# vi_measurement.net
KiCad netlist of a schematic drawn in Altium Designer
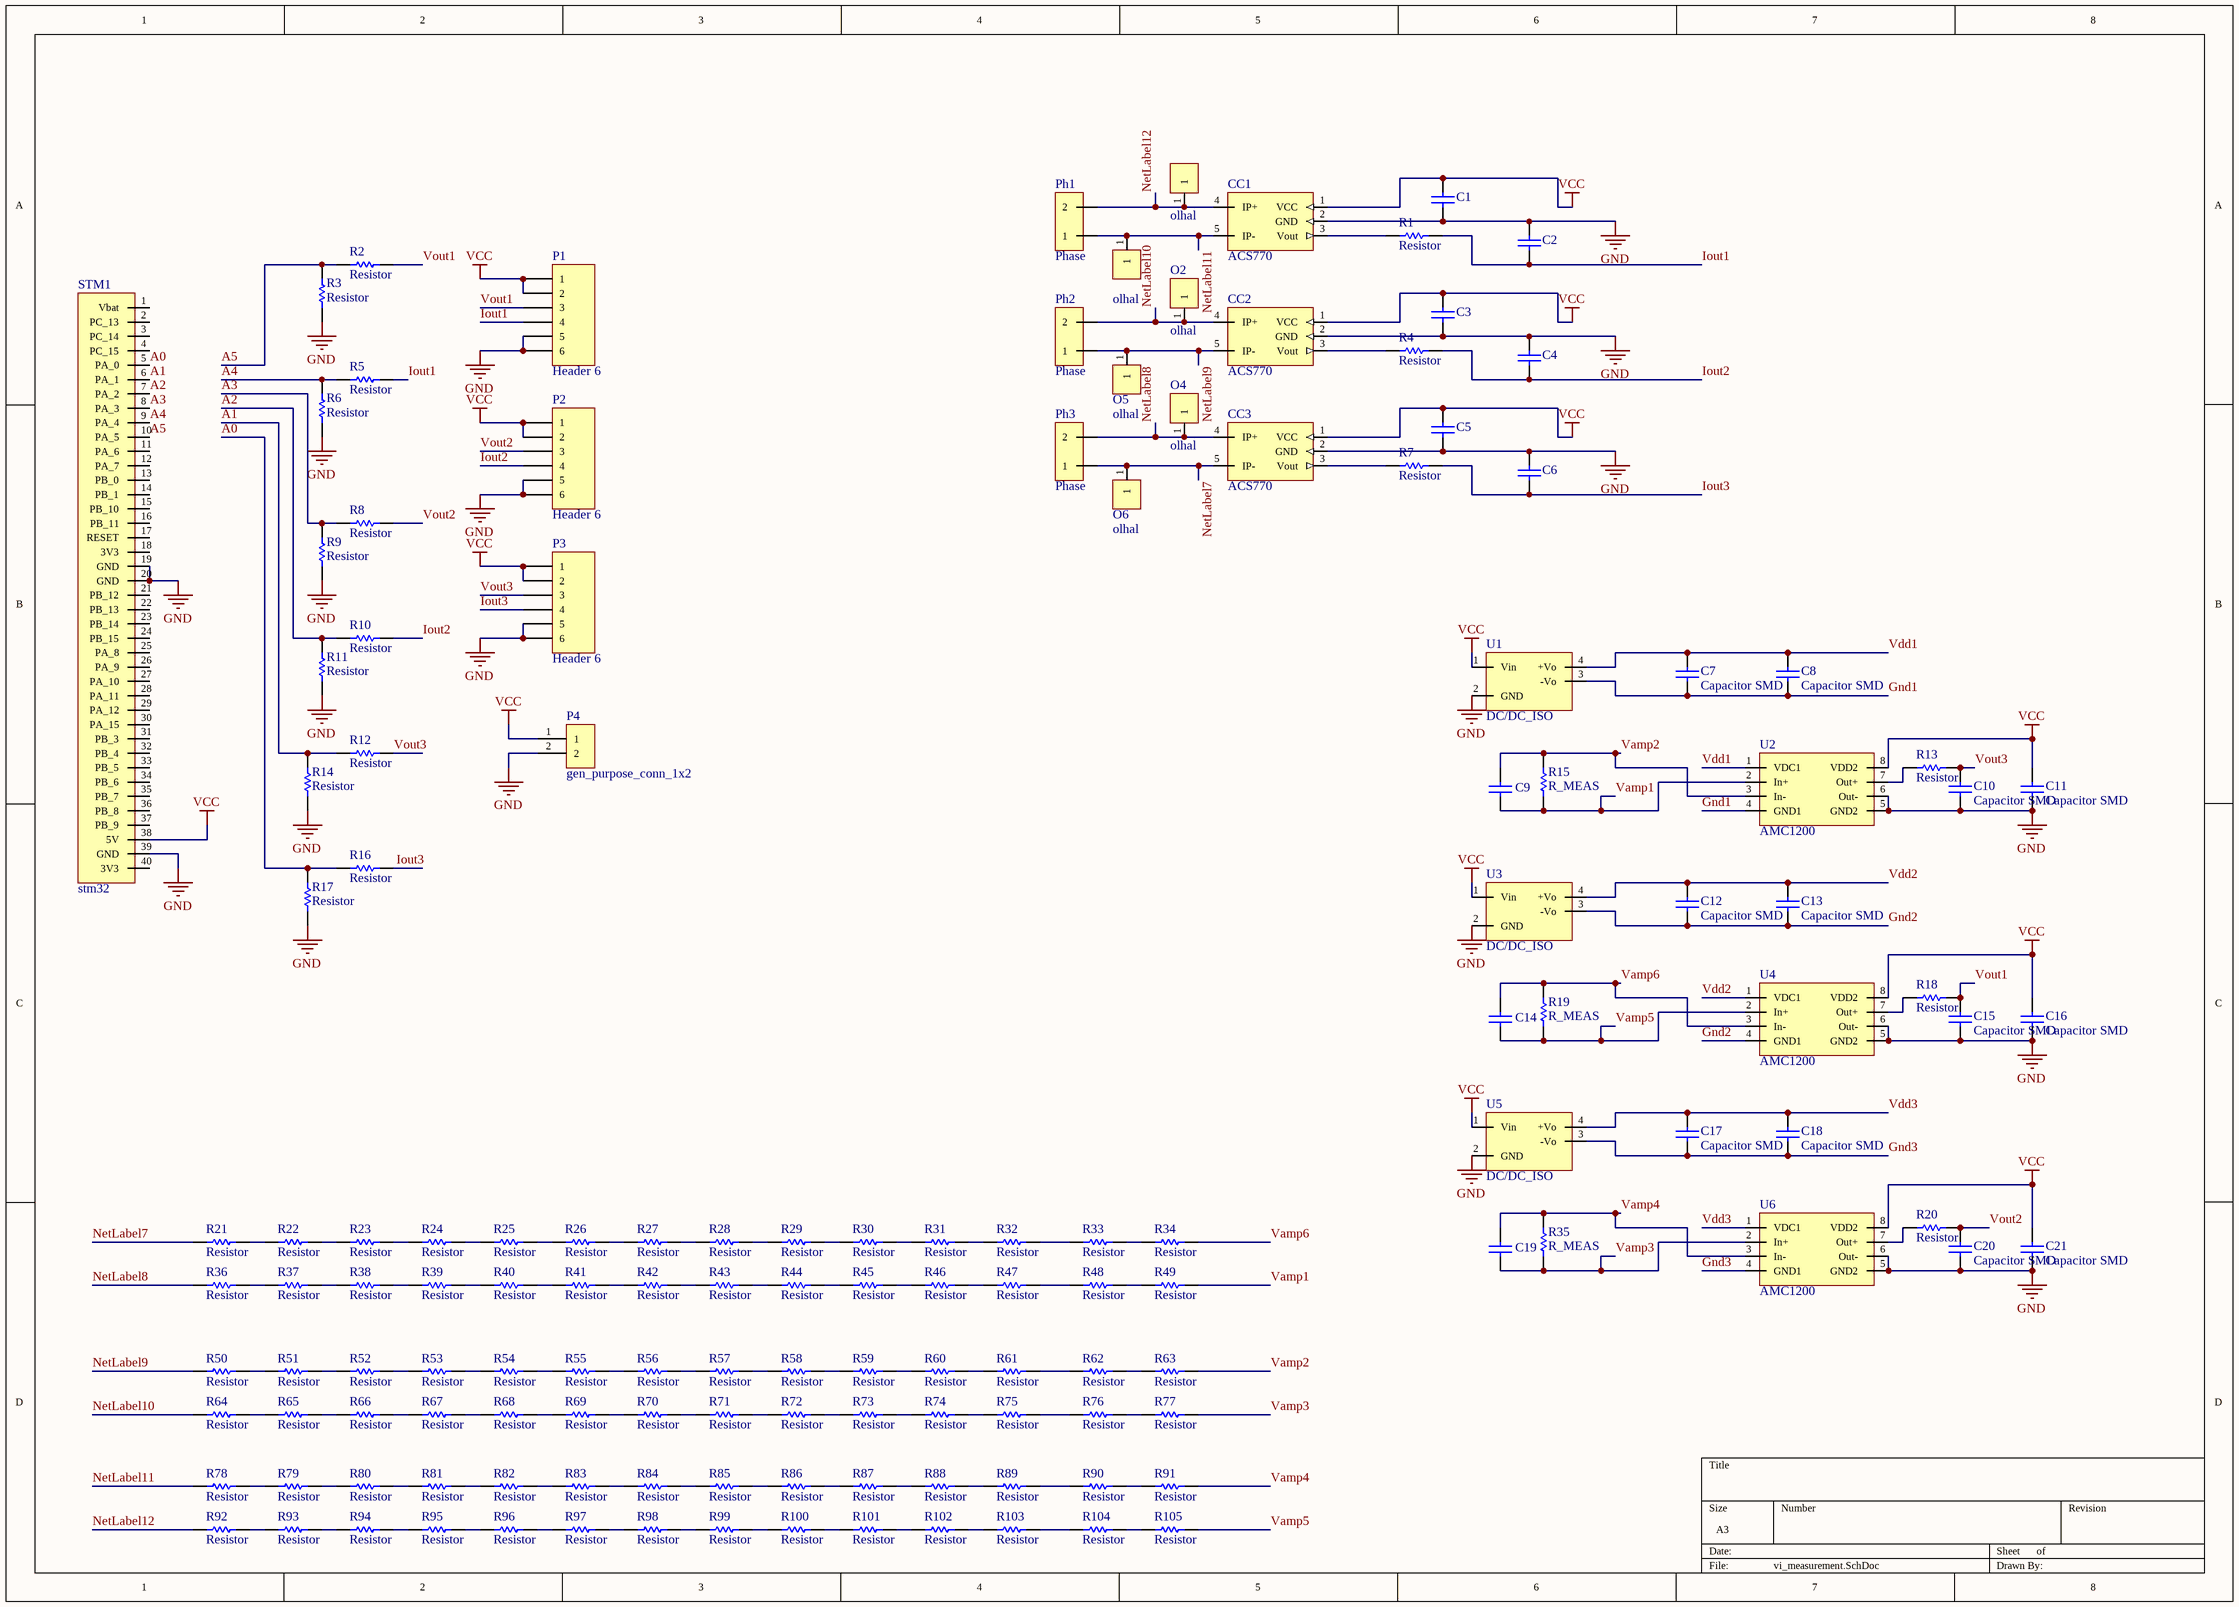
[diagram p0: vi_measurement.SchDoc]

(export (version "E")
  (design (tool "Eeschema 10.0.6"))
  (components
    (comp (ref "C1")
      (value "~")
      (footprint "CAPC_0805")
      (description "10uF")
      (libsource (lib "inversor_50a") (part "Capacitor SMD"))
    )
    (comp (ref "C2")
      (value "~")
      (footprint "CAPC_0805")
      (description "1uF")
      (libsource (lib "inversor_50a") (part "Capacitor SMD"))
    )
    (comp (ref "C3")
      (value "~")
      (footprint "CAPC_0805")
      (description "10uF")
      (libsource (lib "inversor_50a") (part "Capacitor SMD"))
    )
    (comp (ref "C4")
      (value "~")
      (footprint "CAPC_0805")
      (description "1uF")
      (libsource (lib "inversor_50a") (part "Capacitor SMD"))
    )
    (comp (ref "C5")
      (value "~")
      (footprint "CAPC_0805")
      (description "10uF")
      (libsource (lib "inversor_50a") (part "Capacitor SMD"))
    )
    (comp (ref "C6")
      (value "~")
      (footprint "CAPC_0805")
      (description "1uF")
      (libsource (lib "inversor_50a") (part "Capacitor SMD"))
    )
    (comp (ref "C7")
      (value "Capacitor SMD")
      (footprint "CAPC_0805")
      (description "10uF")
      (libsource (lib "vi_measurement") (part "Capacitor SMD"))
    )
    (comp (ref "C8")
      (value "Capacitor SMD")
      (footprint "CAPC_0805")
      (description "10uF")
      (libsource (lib "vi_measurement") (part "Capacitor SMD"))
    )
    (comp (ref "C9")
      (value "Capacitor SMD")
      (footprint "CAPC_0805")
      (description "1uF")
      (libsource (lib "vi_measurement") (part "Capacitor SMD"))
    )
    (comp (ref "C10")
      (value "Capacitor SMD")
      (footprint "CAPC_0805")
      (description "1uF")
      (libsource (lib "vi_measurement") (part "Capacitor SMD"))
    )
    (comp (ref "C11")
      (value "Capacitor SMD")
      (footprint "CAPC_0805")
      (description "10uF")
      (libsource (lib "vi_measurement") (part "Capacitor SMD"))
    )
    (comp (ref "C12")
      (value "Capacitor SMD")
      (footprint "CAPC_0805")
      (description "10uF")
      (libsource (lib "vi_measurement") (part "Capacitor SMD"))
    )
    (comp (ref "C13")
      (value "Capacitor SMD")
      (footprint "CAPC_0805")
      (description "10uF")
      (libsource (lib "vi_measurement") (part "Capacitor SMD"))
    )
    (comp (ref "C14")
      (value "Capacitor SMD")
      (footprint "CAPC_0805")
      (description "1uF")
      (libsource (lib "vi_measurement") (part "Capacitor SMD"))
    )
    (comp (ref "C15")
      (value "Capacitor SMD")
      (footprint "CAPC_0805")
      (description "1uF")
      (libsource (lib "vi_measurement") (part "Capacitor SMD"))
    )
    (comp (ref "C16")
      (value "Capacitor SMD")
      (footprint "CAPC_0805")
      (description "10uF")
      (libsource (lib "vi_measurement") (part "Capacitor SMD"))
    )
    (comp (ref "C17")
      (value "Capacitor SMD")
      (footprint "CAPC_0805")
      (description "10uF")
      (libsource (lib "vi_measurement") (part "Capacitor SMD"))
    )
    (comp (ref "C18")
      (value "Capacitor SMD")
      (footprint "CAPC_0805")
      (description "10uF")
      (libsource (lib "vi_measurement") (part "Capacitor SMD"))
    )
    (comp (ref "C19")
      (value "Capacitor SMD")
      (footprint "CAPC_0805")
      (description "1uF")
      (libsource (lib "vi_measurement") (part "Capacitor SMD"))
    )
    (comp (ref "C20")
      (value "Capacitor SMD")
      (footprint "CAPC_0805")
      (description "1uF")
      (libsource (lib "vi_measurement") (part "Capacitor SMD"))
    )
    (comp (ref "C21")
      (value "Capacitor SMD")
      (footprint "CAPC_0805")
      (description "10uF")
      (libsource (lib "vi_measurement") (part "Capacitor SMD"))
    )
    (comp (ref "CC1") (value "ACS770") (footprint "ACS770") (libsource (lib "malvega_pcb") (part "ACS770")))
    (comp (ref "CC2") (value "ACS770") (footprint "ACS770") (libsource (lib "malvega_pcb") (part "ACS770")))
    (comp (ref "CC3") (value "ACS770") (footprint "ACS770") (libsource (lib "malvega_pcb") (part "ACS770")))
    (comp (ref "O1") (value "olhal") (footprint "Olhal") (libsource (lib "") (part "olhal_1")))
    (comp (ref "O2") (value "olhal") (footprint "Olhal") (libsource (lib "") (part "olhal_1")))
    (comp (ref "O3") (value "olhal") (footprint "Olhal") (libsource (lib "vi_measurement") (part "olhal")))
    (comp (ref "O4") (value "olhal") (footprint "Olhal") (libsource (lib "") (part "olhal_1")))
    (comp (ref "O5") (value "olhal") (footprint "Olhal") (libsource (lib "vi_measurement") (part "olhal")))
    (comp (ref "O6") (value "olhal") (footprint "Olhal") (libsource (lib "vi_measurement") (part "olhal")))
    (comp (ref "P1")
      (value "Header 6")
      (footprint "HDR1X6")
      (description "Header, 6-Pin")
      (fields (field (name "PUBLISHER") "Altium Limited"))
      (libsource (lib "malvega_pcb") (part "Header 6"))
    )
    (comp (ref "P2")
      (value "Header 6")
      (footprint "HDR1X6")
      (description "Header, 6-Pin")
      (fields (field (name "PUBLISHER") "Altium Limited"))
      (libsource (lib "malvega_pcb") (part "Header 6"))
    )
    (comp (ref "P3")
      (value "Header 6")
      (footprint "HDR1X6")
      (description "Header, 6-Pin")
      (fields (field (name "PUBLISHER") "Altium Limited"))
      (libsource (lib "malvega_pcb") (part "Header 6"))
    )
    (comp (ref "P4")
      (value "gen_purpose_conn_1x2")
      (footprint "connector1x2_parafuso")
      (libsource (lib "malvega_pcb") (part "gen_purpose_conn_1x2"))
    )
    (comp (ref "Ph1") (value "Phase") (footprint "Phoenix") (libsource (lib "malvega_pcb") (part "Phoenix")))
    (comp (ref "Ph2") (value "Phase") (footprint "Phoenix") (libsource (lib "malvega_pcb") (part "Phoenix")))
    (comp (ref "Ph3") (value "Phase") (footprint "Phoenix") (libsource (lib "malvega_pcb") (part "Phoenix")))
    (comp (ref "R1")
      (value "Resistor")
      (footprint "RESC_0805")
      (description "330R")
      (libsource (lib "inversor_50a") (part "Resistor"))
    )
    (comp (ref "R2")
      (value "Resistor")
      (footprint "RESC_0805")
      (description "5K")
      (libsource (lib "inversor_50a") (part "Resistor"))
    )
    (comp (ref "R3")
      (value "Resistor")
      (footprint "RESC_0805")
      (description "7K5")
      (libsource (lib "inversor_50a") (part "Resistor"))
    )
    (comp (ref "R4")
      (value "Resistor")
      (footprint "RESC_0805")
      (description "330R")
      (libsource (lib "inversor_50a") (part "Resistor"))
    )
    (comp (ref "R5")
      (value "Resistor")
      (footprint "RESC_0805")
      (description "5K")
      (libsource (lib "inversor_50a") (part "Resistor"))
    )
    (comp (ref "R6")
      (value "Resistor")
      (footprint "RESC_0805")
      (description "7K5")
      (libsource (lib "inversor_50a") (part "Resistor"))
    )
    (comp (ref "R7")
      (value "Resistor")
      (footprint "RESC_0805")
      (description "330R")
      (libsource (lib "inversor_50a") (part "Resistor"))
    )
    (comp (ref "R8")
      (value "Resistor")
      (footprint "RESC_0805")
      (description "5K")
      (libsource (lib "inversor_50a") (part "Resistor"))
    )
    (comp (ref "R9")
      (value "Resistor")
      (footprint "RESC_0805")
      (description "7K5")
      (libsource (lib "inversor_50a") (part "Resistor"))
    )
    (comp (ref "R10")
      (value "Resistor")
      (footprint "RESC_0805")
      (description "5K")
      (libsource (lib "inversor_50a") (part "Resistor"))
    )
    (comp (ref "R11")
      (value "Resistor")
      (footprint "RESC_0805")
      (description "7K5")
      (libsource (lib "inversor_50a") (part "Resistor"))
    )
    (comp (ref "R12")
      (value "Resistor")
      (footprint "RESC_0805")
      (description "5K")
      (libsource (lib "inversor_50a") (part "Resistor"))
    )
    (comp (ref "R13")
      (value "Resistor")
      (footprint "RESC_0805")
      (description "330R")
      (libsource (lib "inversor_50a") (part "Resistor"))
    )
    (comp (ref "R14")
      (value "Resistor")
      (footprint "RESC_0805")
      (description "7K5")
      (libsource (lib "inversor_50a") (part "Resistor"))
    )
    (comp (ref "R15")
      (value "R_MEAS")
      (footprint "RESC_0805")
      (description "200R")
      (libsource (lib "inversor_50a") (part "Resistor"))
    )
    (comp (ref "R16")
      (value "Resistor")
      (footprint "RESC_0805")
      (description "5K")
      (libsource (lib "inversor_50a") (part "Resistor"))
    )
    (comp (ref "R17")
      (value "Resistor")
      (footprint "RESC_0805")
      (description "7K5")
      (libsource (lib "inversor_50a") (part "Resistor"))
    )
    (comp (ref "R18")
      (value "Resistor")
      (footprint "RESC_0805")
      (description "330R")
      (libsource (lib "inversor_50a") (part "Resistor"))
    )
    (comp (ref "R19")
      (value "R_MEAS")
      (footprint "RESC_0805")
      (description "200R")
      (libsource (lib "inversor_50a") (part "Resistor"))
    )
    (comp (ref "R20")
      (value "Resistor")
      (footprint "RESC_0805")
      (description "330R")
      (libsource (lib "inversor_50a") (part "Resistor"))
    )
    (comp (ref "R21")
      (value "Resistor")
      (footprint "RESC_0805")
      (description "7K5")
      (libsource (lib "inversor_50a") (part "Resistor"))
    )
    (comp (ref "R22")
      (value "Resistor")
      (footprint "RESC_0805")
      (libsource (lib "inversor_50a") (part "Resistor"))
    )
    (comp (ref "R23")
      (value "Resistor")
      (footprint "RESC_0805")
      (libsource (lib "inversor_50a") (part "Resistor"))
    )
    (comp (ref "R24")
      (value "Resistor")
      (footprint "RESC_0805")
      (libsource (lib "inversor_50a") (part "Resistor"))
    )
    (comp (ref "R25")
      (value "Resistor")
      (footprint "RESC_0805")
      (libsource (lib "inversor_50a") (part "Resistor"))
    )
    (comp (ref "R26")
      (value "Resistor")
      (footprint "RESC_0805")
      (libsource (lib "inversor_50a") (part "Resistor"))
    )
    (comp (ref "R27")
      (value "Resistor")
      (footprint "RESC_0805")
      (libsource (lib "inversor_50a") (part "Resistor"))
    )
    (comp (ref "R28")
      (value "Resistor")
      (footprint "RESC_0805")
      (libsource (lib "inversor_50a") (part "Resistor"))
    )
    (comp (ref "R29")
      (value "Resistor")
      (footprint "RESC_0805")
      (libsource (lib "inversor_50a") (part "Resistor"))
    )
    (comp (ref "R30")
      (value "Resistor")
      (footprint "RESC_0805")
      (libsource (lib "inversor_50a") (part "Resistor"))
    )
    (comp (ref "R31")
      (value "Resistor")
      (footprint "RESC_0805")
      (libsource (lib "inversor_50a") (part "Resistor"))
    )
    (comp (ref "R32")
      (value "Resistor")
      (footprint "RESC_0805")
      (libsource (lib "inversor_50a") (part "Resistor"))
    )
    (comp (ref "R33")
      (value "Resistor")
      (footprint "RESC_0805")
      (libsource (lib "inversor_50a") (part "Resistor"))
    )
    (comp (ref "R34")
      (value "Resistor")
      (footprint "RESC_0805")
      (libsource (lib "inversor_50a") (part "Resistor"))
    )
    (comp (ref "R35")
      (value "R_MEAS")
      (footprint "RESC_0805")
      (description "200R")
      (libsource (lib "inversor_50a") (part "Resistor"))
    )
    (comp (ref "R36")
      (value "Resistor")
      (footprint "RESC_0805")
      (description "7K5")
      (libsource (lib "inversor_50a") (part "Resistor"))
    )
    (comp (ref "R37")
      (value "Resistor")
      (footprint "RESC_0805")
      (description "7K5")
      (libsource (lib "inversor_50a") (part "Resistor"))
    )
    (comp (ref "R38")
      (value "Resistor")
      (footprint "RESC_0805")
      (description "7K5")
      (libsource (lib "inversor_50a") (part "Resistor"))
    )
    (comp (ref "R39")
      (value "Resistor")
      (footprint "RESC_0805")
      (description "7K5")
      (libsource (lib "inversor_50a") (part "Resistor"))
    )
    (comp (ref "R40")
      (value "Resistor")
      (footprint "RESC_0805")
      (description "7K5")
      (libsource (lib "inversor_50a") (part "Resistor"))
    )
    (comp (ref "R41")
      (value "Resistor")
      (footprint "RESC_0805")
      (description "7K5")
      (libsource (lib "inversor_50a") (part "Resistor"))
    )
    (comp (ref "R42")
      (value "Resistor")
      (footprint "RESC_0805")
      (description "7K5")
      (libsource (lib "inversor_50a") (part "Resistor"))
    )
    (comp (ref "R43")
      (value "Resistor")
      (footprint "RESC_0805")
      (description "7K5")
      (libsource (lib "inversor_50a") (part "Resistor"))
    )
    (comp (ref "R44")
      (value "Resistor")
      (footprint "RESC_0805")
      (description "7K5")
      (libsource (lib "inversor_50a") (part "Resistor"))
    )
    (comp (ref "R45")
      (value "Resistor")
      (footprint "RESC_0805")
      (description "7K5")
      (libsource (lib "inversor_50a") (part "Resistor"))
    )
    (comp (ref "R46")
      (value "Resistor")
      (footprint "RESC_0805")
      (description "7K5")
      (libsource (lib "inversor_50a") (part "Resistor"))
    )
    (comp (ref "R47")
      (value "Resistor")
      (footprint "RESC_0805")
      (description "7K5")
      (libsource (lib "inversor_50a") (part "Resistor"))
    )
    (comp (ref "R48")
      (value "Resistor")
      (footprint "RESC_0805")
      (description "7K5")
      (libsource (lib "inversor_50a") (part "Resistor"))
    )
    (comp (ref "R49")
      (value "Resistor")
      (footprint "RESC_0805")
      (description "7K5")
      (libsource (lib "inversor_50a") (part "Resistor"))
    )
    (comp (ref "R50")
      (value "Resistor")
      (footprint "RESC_0805")
      (description "7K5")
      (libsource (lib "inversor_50a") (part "Resistor"))
    )
    (comp (ref "R51")
      (value "Resistor")
      (footprint "RESC_0805")
      (description "7K5")
      (libsource (lib "inversor_50a") (part "Resistor"))
    )
    (comp (ref "R52")
      (value "Resistor")
      (footprint "RESC_0805")
      (description "7K5")
      (libsource (lib "inversor_50a") (part "Resistor"))
    )
    (comp (ref "R53")
      (value "Resistor")
      (footprint "RESC_0805")
      (description "7K5")
      (libsource (lib "inversor_50a") (part "Resistor"))
    )
    (comp (ref "R54")
      (value "Resistor")
      (footprint "RESC_0805")
      (description "7K5")
      (libsource (lib "inversor_50a") (part "Resistor"))
    )
    (comp (ref "R55")
      (value "Resistor")
      (footprint "RESC_0805")
      (description "7K5")
      (libsource (lib "inversor_50a") (part "Resistor"))
    )
    (comp (ref "R56")
      (value "Resistor")
      (footprint "RESC_0805")
      (description "7K5")
      (libsource (lib "inversor_50a") (part "Resistor"))
    )
    (comp (ref "R57")
      (value "Resistor")
      (footprint "RESC_0805")
      (description "7K5")
      (libsource (lib "inversor_50a") (part "Resistor"))
    )
    (comp (ref "R58")
      (value "Resistor")
      (footprint "RESC_0805")
      (description "7K5")
      (libsource (lib "inversor_50a") (part "Resistor"))
    )
    (comp (ref "R59")
      (value "Resistor")
      (footprint "RESC_0805")
      (description "7K5")
      (libsource (lib "inversor_50a") (part "Resistor"))
    )
    (comp (ref "R60")
      (value "Resistor")
      (footprint "RESC_0805")
      (description "7K5")
      (libsource (lib "inversor_50a") (part "Resistor"))
    )
    (comp (ref "R61")
      (value "Resistor")
      (footprint "RESC_0805")
      (description "7K5")
      (libsource (lib "inversor_50a") (part "Resistor"))
    )
    (comp (ref "R62")
      (value "Resistor")
      (footprint "RESC_0805")
      (description "7K5")
      (libsource (lib "inversor_50a") (part "Resistor"))
    )
    (comp (ref "R63")
      (value "Resistor")
      (footprint "RESC_0805")
      (description "7K5")
      (libsource (lib "inversor_50a") (part "Resistor"))
    )
    (comp (ref "R64")
      (value "Resistor")
      (footprint "RESC_0805")
      (description "7K5")
      (libsource (lib "inversor_50a") (part "Resistor"))
    )
    (comp (ref "R65")
      (value "Resistor")
      (footprint "RESC_0805")
      (description "7K5")
      (libsource (lib "inversor_50a") (part "Resistor"))
    )
    (comp (ref "R66")
      (value "Resistor")
      (footprint "RESC_0805")
      (description "7K5")
      (libsource (lib "inversor_50a") (part "Resistor"))
    )
    (comp (ref "R67")
      (value "Resistor")
      (footprint "RESC_0805")
      (description "7K5")
      (libsource (lib "inversor_50a") (part "Resistor"))
    )
    (comp (ref "R68")
      (value "Resistor")
      (footprint "RESC_0805")
      (description "7K5")
      (libsource (lib "inversor_50a") (part "Resistor"))
    )
    (comp (ref "R69")
      (value "Resistor")
      (footprint "RESC_0805")
      (description "7K5")
      (libsource (lib "inversor_50a") (part "Resistor"))
    )
    (comp (ref "R70")
      (value "Resistor")
      (footprint "RESC_0805")
      (description "7K5")
      (libsource (lib "inversor_50a") (part "Resistor"))
    )
    (comp (ref "R71")
      (value "Resistor")
      (footprint "RESC_0805")
      (description "7K5")
      (libsource (lib "inversor_50a") (part "Resistor"))
    )
    (comp (ref "R72")
      (value "Resistor")
      (footprint "RESC_0805")
      (description "7K5")
      (libsource (lib "inversor_50a") (part "Resistor"))
    )
    (comp (ref "R73")
      (value "Resistor")
      (footprint "RESC_0805")
      (description "7K5")
      (libsource (lib "inversor_50a") (part "Resistor"))
    )
    (comp (ref "R74")
      (value "Resistor")
      (footprint "RESC_0805")
      (description "7K5")
      (libsource (lib "inversor_50a") (part "Resistor"))
    )
    (comp (ref "R75")
      (value "Resistor")
      (footprint "RESC_0805")
      (description "7K5")
      (libsource (lib "inversor_50a") (part "Resistor"))
    )
    (comp (ref "R76")
      (value "Resistor")
      (footprint "RESC_0805")
      (description "7K5")
      (libsource (lib "inversor_50a") (part "Resistor"))
    )
    (comp (ref "R77")
      (value "Resistor")
      (footprint "RESC_0805")
      (description "7K5")
      (libsource (lib "inversor_50a") (part "Resistor"))
    )
    (comp (ref "R78")
      (value "Resistor")
      (footprint "RESC_0805")
      (description "7K5")
      (libsource (lib "inversor_50a") (part "Resistor"))
    )
    (comp (ref "R79")
      (value "Resistor")
      (footprint "RESC_0805")
      (description "7K5")
      (libsource (lib "inversor_50a") (part "Resistor"))
    )
    (comp (ref "R80")
      (value "Resistor")
      (footprint "RESC_0805")
      (description "7K5")
      (libsource (lib "inversor_50a") (part "Resistor"))
    )
    (comp (ref "R81")
      (value "Resistor")
      (footprint "RESC_0805")
      (description "7K5")
      (libsource (lib "inversor_50a") (part "Resistor"))
    )
    (comp (ref "R82")
      (value "Resistor")
      (footprint "RESC_0805")
      (description "7K5")
      (libsource (lib "inversor_50a") (part "Resistor"))
    )
    (comp (ref "R83")
      (value "Resistor")
      (footprint "RESC_0805")
      (description "7K5")
      (libsource (lib "inversor_50a") (part "Resistor"))
    )
    (comp (ref "R84")
      (value "Resistor")
      (footprint "RESC_0805")
      (description "7K5")
      (libsource (lib "inversor_50a") (part "Resistor"))
    )
    (comp (ref "R85")
      (value "Resistor")
      (footprint "RESC_0805")
      (description "7K5")
      (libsource (lib "inversor_50a") (part "Resistor"))
    )
    (comp (ref "R86")
      (value "Resistor")
      (footprint "RESC_0805")
      (description "7K5")
      (libsource (lib "inversor_50a") (part "Resistor"))
    )
    (comp (ref "R87")
      (value "Resistor")
      (footprint "RESC_0805")
      (description "7K5")
      (libsource (lib "inversor_50a") (part "Resistor"))
    )
    (comp (ref "R88")
      (value "Resistor")
      (footprint "RESC_0805")
      (description "7K5")
      (libsource (lib "inversor_50a") (part "Resistor"))
    )
    (comp (ref "R89")
      (value "Resistor")
      (footprint "RESC_0805")
      (description "7K5")
      (libsource (lib "inversor_50a") (part "Resistor"))
    )
    (comp (ref "R90")
      (value "Resistor")
      (footprint "RESC_0805")
      (description "7K5")
      (libsource (lib "inversor_50a") (part "Resistor"))
    )
    (comp (ref "R91")
      (value "Resistor")
      (footprint "RESC_0805")
      (description "7K5")
      (libsource (lib "inversor_50a") (part "Resistor"))
    )
    (comp (ref "R92")
      (value "Resistor")
      (footprint "RESC_0805")
      (description "7K5")
      (libsource (lib "inversor_50a") (part "Resistor"))
    )
    (comp (ref "R93")
      (value "Resistor")
      (footprint "RESC_0805")
      (description "7K5")
      (libsource (lib "inversor_50a") (part "Resistor"))
    )
    (comp (ref "R94")
      (value "Resistor")
      (footprint "RESC_0805")
      (description "7K5")
      (libsource (lib "inversor_50a") (part "Resistor"))
    )
    (comp (ref "R95")
      (value "Resistor")
      (footprint "RESC_0805")
      (description "7K5")
      (libsource (lib "inversor_50a") (part "Resistor"))
    )
    (comp (ref "R96")
      (value "Resistor")
      (footprint "RESC_0805")
      (description "7K5")
      (libsource (lib "inversor_50a") (part "Resistor"))
    )
    (comp (ref "R97")
      (value "Resistor")
      (footprint "RESC_0805")
      (description "7K5")
      (libsource (lib "inversor_50a") (part "Resistor"))
    )
    (comp (ref "R98")
      (value "Resistor")
      (footprint "RESC_0805")
      (description "7K5")
      (libsource (lib "inversor_50a") (part "Resistor"))
    )
    (comp (ref "R99")
      (value "Resistor")
      (footprint "RESC_0805")
      (description "7K5")
      (libsource (lib "inversor_50a") (part "Resistor"))
    )
    (comp (ref "R100")
      (value "Resistor")
      (footprint "RESC_0805")
      (description "7K5")
      (libsource (lib "inversor_50a") (part "Resistor"))
    )
    (comp (ref "R101")
      (value "Resistor")
      (footprint "RESC_0805")
      (description "7K5")
      (libsource (lib "inversor_50a") (part "Resistor"))
    )
    (comp (ref "R102")
      (value "Resistor")
      (footprint "RESC_0805")
      (description "7K5")
      (libsource (lib "inversor_50a") (part "Resistor"))
    )
    (comp (ref "R103")
      (value "Resistor")
      (footprint "RESC_0805")
      (description "7K5")
      (libsource (lib "inversor_50a") (part "Resistor"))
    )
    (comp (ref "R104")
      (value "Resistor")
      (footprint "RESC_0805")
      (description "7K5")
      (libsource (lib "inversor_50a") (part "Resistor"))
    )
    (comp (ref "R105")
      (value "Resistor")
      (footprint "RESC_0805")
      (description "7K5")
      (libsource (lib "inversor_50a") (part "Resistor"))
    )
    (comp (ref "STM1") (value "stm32") (footprint "STM32") (libsource (lib "vi_measurement") (part "stm32")))
    (comp (ref "U1")
      (value "DC/DC_ISO")
      (footprint "DC/DC_ISO")
      (libsource (lib "vi_measurement") (part "DC/DC_ISO"))
    )
    (comp (ref "U2")
      (value "AMC1200")
      (footprint "SOIC8")
      (libsource (lib "vi_measurement") (part "AMC1200"))
    )
    (comp (ref "U3")
      (value "DC/DC_ISO")
      (footprint "DC/DC_ISO")
      (libsource (lib "vi_measurement") (part "DC/DC_ISO"))
    )
    (comp (ref "U4")
      (value "AMC1200")
      (footprint "SOIC8")
      (libsource (lib "vi_measurement") (part "AMC1200"))
    )
    (comp (ref "U5")
      (value "DC/DC_ISO")
      (footprint "DC/DC_ISO")
      (libsource (lib "vi_measurement") (part "DC/DC_ISO"))
    )
    (comp (ref "U6")
      (value "AMC1200")
      (footprint "SOIC8")
      (libsource (lib "vi_measurement") (part "AMC1200"))
    )
  )
  (nets
    (net (code "1") (name "/A0") (class "Default")
      (node (ref "R16") (pin "1") (pinfunction "1_1") (pintype "passive"))
      (node (ref "R17") (pin "2") (pinfunction "2_2") (pintype "passive"))
      (node (ref "STM1") (pin "5") (pinfunction "PA_0_5") (pintype "passive"))
    )
    (net (code "2") (name "/A1") (class "Default")
      (node (ref "R12") (pin "1") (pinfunction "1_1") (pintype "passive"))
      (node (ref "R14") (pin "2") (pinfunction "2_2") (pintype "passive"))
      (node (ref "STM1") (pin "6") (pinfunction "PA_1_6") (pintype "passive"))
    )
    (net (code "3") (name "/A2") (class "Default")
      (node (ref "R10") (pin "1") (pinfunction "1_1") (pintype "passive"))
      (node (ref "R11") (pin "2") (pinfunction "2_2") (pintype "passive"))
      (node (ref "STM1") (pin "7") (pinfunction "PA_2_7") (pintype "passive"))
    )
    (net (code "4") (name "/A3") (class "Default")
      (node (ref "R8") (pin "1") (pinfunction "1_1") (pintype "passive"))
      (node (ref "R9") (pin "2") (pinfunction "2_2") (pintype "passive"))
      (node (ref "STM1") (pin "8") (pinfunction "PA_3_8") (pintype "passive"))
    )
    (net (code "5") (name "/A4") (class "Default")
      (node (ref "R5") (pin "1") (pinfunction "1_1") (pintype "passive"))
      (node (ref "R6") (pin "2") (pinfunction "2_2") (pintype "passive"))
      (node (ref "STM1") (pin "9") (pinfunction "PA_4_9") (pintype "passive"))
    )
    (net (code "6") (name "/A5") (class "Default")
      (node (ref "R2") (pin "1") (pinfunction "1_1") (pintype "passive"))
      (node (ref "R3") (pin "2") (pinfunction "2_2") (pintype "passive"))
      (node (ref "STM1") (pin "10") (pinfunction "PA_5_10") (pintype "passive"))
    )
    (net (code "7") (name "/Gnd1") (class "Default")
      (node (ref "C7") (pin "1") (pinfunction "1_1") (pintype "passive"))
      (node (ref "C8") (pin "1") (pinfunction "1_1") (pintype "passive"))
      (node (ref "U1") (pin "3") (pinfunction "-Vo_3") (pintype "passive"))
      (node (ref "U2") (pin "4") (pinfunction "GND1_4") (pintype "passive"))
    )
    (net (code "8") (name "/Gnd2") (class "Default")
      (node (ref "C12") (pin "1") (pinfunction "1_1") (pintype "passive"))
      (node (ref "C13") (pin "1") (pinfunction "1_1") (pintype "passive"))
      (node (ref "U3") (pin "3") (pinfunction "-Vo_3") (pintype "passive"))
      (node (ref "U4") (pin "4") (pinfunction "GND1_4") (pintype "passive"))
    )
    (net (code "9") (name "/Gnd3") (class "Default")
      (node (ref "C17") (pin "1") (pinfunction "1_1") (pintype "passive"))
      (node (ref "C18") (pin "1") (pinfunction "1_1") (pintype "passive"))
      (node (ref "U5") (pin "3") (pinfunction "-Vo_3") (pintype "passive"))
      (node (ref "U6") (pin "4") (pinfunction "GND1_4") (pintype "passive"))
    )
    (net (code "10") (name "/Iout1") (class "Default")
      (node (ref "C2") (pin "1") (pinfunction "1_1") (pintype "passive"))
      (node (ref "P1") (pin "4") (pinfunction "4_4") (pintype "passive"))
      (node (ref "R1") (pin "2") (pinfunction "2_2") (pintype "passive"))
      (node (ref "R5") (pin "2") (pinfunction "2_2") (pintype "passive"))
    )
    (net (code "11") (name "/Iout2") (class "Default")
      (node (ref "C4") (pin "1") (pinfunction "1_1") (pintype "passive"))
      (node (ref "P2") (pin "4") (pinfunction "4_4") (pintype "passive"))
      (node (ref "R10") (pin "2") (pinfunction "2_2") (pintype "passive"))
      (node (ref "R4") (pin "2") (pinfunction "2_2") (pintype "passive"))
    )
    (net (code "12") (name "/Iout3") (class "Default")
      (node (ref "C6") (pin "1") (pinfunction "1_1") (pintype "passive"))
      (node (ref "P3") (pin "4") (pinfunction "4_4") (pintype "passive"))
      (node (ref "R16") (pin "2") (pinfunction "2_2") (pintype "passive"))
      (node (ref "R7") (pin "2") (pinfunction "2_2") (pintype "passive"))
    )
    (net (code "13") (name "/NetLabel7") (class "Default")
      (node (ref "CC3") (pin "5") (pinfunction "IP-_5") (pintype "power_in"))
      (node (ref "O6") (pin "1") (pinfunction "1_1") (pintype "passive"))
      (node (ref "Ph3") (pin "1") (pinfunction "1_1") (pintype "passive"))
      (node (ref "R21") (pin "1") (pinfunction "1_1") (pintype "passive"))
    )
    (net (code "14") (name "/NetLabel8") (class "Default")
      (node (ref "CC3") (pin "4") (pinfunction "IP+_4") (pintype "power_in"))
      (node (ref "O4") (pin "1") (pinfunction "1_1") (pintype "passive"))
      (node (ref "Ph3") (pin "2") (pinfunction "2_2") (pintype "passive"))
      (node (ref "R36") (pin "1") (pinfunction "1_1") (pintype "passive"))
    )
    (net (code "15") (name "/NetLabel9") (class "Default")
      (node (ref "CC2") (pin "5") (pinfunction "IP-_5") (pintype "power_in"))
      (node (ref "O5") (pin "1") (pinfunction "1_1") (pintype "passive"))
      (node (ref "Ph2") (pin "1") (pinfunction "1_1") (pintype "passive"))
      (node (ref "R50") (pin "1") (pinfunction "1_1") (pintype "passive"))
    )
    (net (code "16") (name "/NetLabel10") (class "Default")
      (node (ref "CC2") (pin "4") (pinfunction "IP+_4") (pintype "power_in"))
      (node (ref "O2") (pin "1") (pinfunction "1_1") (pintype "passive"))
      (node (ref "Ph2") (pin "2") (pinfunction "2_2") (pintype "passive"))
      (node (ref "R64") (pin "1") (pinfunction "1_1") (pintype "passive"))
    )
    (net (code "17") (name "/NetLabel11") (class "Default")
      (node (ref "CC1") (pin "5") (pinfunction "IP-_5") (pintype "power_in"))
      (node (ref "O3") (pin "1") (pinfunction "1_1") (pintype "passive"))
      (node (ref "Ph1") (pin "1") (pinfunction "1_1") (pintype "passive"))
      (node (ref "R78") (pin "1") (pinfunction "1_1") (pintype "passive"))
    )
    (net (code "18") (name "/NetLabel12") (class "Default")
      (node (ref "CC1") (pin "4") (pinfunction "IP+_4") (pintype "power_in"))
      (node (ref "O1") (pin "1") (pinfunction "1_1") (pintype "passive"))
      (node (ref "Ph1") (pin "2") (pinfunction "2_2") (pintype "passive"))
      (node (ref "R92") (pin "1") (pinfunction "1_1") (pintype "passive"))
    )
    (net (code "19") (name "/Vamp1") (class "Default")
      (node (ref "C9") (pin "1") (pinfunction "1_1") (pintype "passive"))
      (node (ref "R15") (pin "1") (pinfunction "1_1") (pintype "passive"))
      (node (ref "R49") (pin "2") (pinfunction "2_2") (pintype "passive"))
      (node (ref "U2") (pin "2") (pinfunction "In+_2") (pintype "passive"))
    )
    (net (code "20") (name "/Vamp2") (class "Default")
      (node (ref "C9") (pin "2") (pinfunction "2_2") (pintype "passive"))
      (node (ref "R15") (pin "2") (pinfunction "2_2") (pintype "passive"))
      (node (ref "R63") (pin "2") (pinfunction "2_2") (pintype "passive"))
      (node (ref "U2") (pin "3") (pinfunction "In-_3") (pintype "passive"))
    )
    (net (code "21") (name "/Vamp3") (class "Default")
      (node (ref "C19") (pin "1") (pinfunction "1_1") (pintype "passive"))
      (node (ref "R35") (pin "1") (pinfunction "1_1") (pintype "passive"))
      (node (ref "R77") (pin "2") (pinfunction "2_2") (pintype "passive"))
      (node (ref "U6") (pin "2") (pinfunction "In+_2") (pintype "passive"))
    )
    (net (code "22") (name "/Vamp4") (class "Default")
      (node (ref "C19") (pin "2") (pinfunction "2_2") (pintype "passive"))
      (node (ref "R35") (pin "2") (pinfunction "2_2") (pintype "passive"))
      (node (ref "R91") (pin "2") (pinfunction "2_2") (pintype "passive"))
      (node (ref "U6") (pin "3") (pinfunction "In-_3") (pintype "passive"))
    )
    (net (code "23") (name "/Vamp5") (class "Default")
      (node (ref "C14") (pin "1") (pinfunction "1_1") (pintype "passive"))
      (node (ref "R105") (pin "2") (pinfunction "2_2") (pintype "passive"))
      (node (ref "R19") (pin "1") (pinfunction "1_1") (pintype "passive"))
      (node (ref "U4") (pin "2") (pinfunction "In+_2") (pintype "passive"))
    )
    (net (code "24") (name "/Vamp6") (class "Default")
      (node (ref "C14") (pin "2") (pinfunction "2_2") (pintype "passive"))
      (node (ref "R19") (pin "2") (pinfunction "2_2") (pintype "passive"))
      (node (ref "R34") (pin "2") (pinfunction "2_2") (pintype "passive"))
      (node (ref "U4") (pin "3") (pinfunction "In-_3") (pintype "passive"))
    )
    (net (code "25") (name "/Vdd1") (class "Default")
      (node (ref "C7") (pin "2") (pinfunction "2_2") (pintype "passive"))
      (node (ref "C8") (pin "2") (pinfunction "2_2") (pintype "passive"))
      (node (ref "U1") (pin "4") (pinfunction "+Vo_4") (pintype "passive"))
      (node (ref "U2") (pin "1") (pinfunction "VDC1_1") (pintype "passive"))
    )
    (net (code "26") (name "/Vdd2") (class "Default")
      (node (ref "C12") (pin "2") (pinfunction "2_2") (pintype "passive"))
      (node (ref "C13") (pin "2") (pinfunction "2_2") (pintype "passive"))
      (node (ref "U3") (pin "4") (pinfunction "+Vo_4") (pintype "passive"))
      (node (ref "U4") (pin "1") (pinfunction "VDC1_1") (pintype "passive"))
    )
    (net (code "27") (name "/Vdd3") (class "Default")
      (node (ref "C17") (pin "2") (pinfunction "2_2") (pintype "passive"))
      (node (ref "C18") (pin "2") (pinfunction "2_2") (pintype "passive"))
      (node (ref "U5") (pin "4") (pinfunction "+Vo_4") (pintype "passive"))
      (node (ref "U6") (pin "1") (pinfunction "VDC1_1") (pintype "passive"))
    )
    (net (code "28") (name "/Vout1") (class "Default")
      (node (ref "C15") (pin "2") (pinfunction "2_2") (pintype "passive"))
      (node (ref "P1") (pin "3") (pinfunction "3_3") (pintype "passive"))
      (node (ref "R18") (pin "2") (pinfunction "2_2") (pintype "passive"))
      (node (ref "R2") (pin "2") (pinfunction "2_2") (pintype "passive"))
    )
    (net (code "29") (name "/Vout2") (class "Default")
      (node (ref "C20") (pin "2") (pinfunction "2_2") (pintype "passive"))
      (node (ref "P2") (pin "3") (pinfunction "3_3") (pintype "passive"))
      (node (ref "R20") (pin "2") (pinfunction "2_2") (pintype "passive"))
      (node (ref "R8") (pin "2") (pinfunction "2_2") (pintype "passive"))
    )
    (net (code "30") (name "/Vout3") (class "Default")
      (node (ref "C10") (pin "2") (pinfunction "2_2") (pintype "passive"))
      (node (ref "P3") (pin "3") (pinfunction "3_3") (pintype "passive"))
      (node (ref "R12") (pin "2") (pinfunction "2_2") (pintype "passive"))
      (node (ref "R13") (pin "2") (pinfunction "2_2") (pintype "passive"))
    )
    (net (code "31") (name "GND") (class "Default")
      (node (ref "C1") (pin "1") (pinfunction "1_1") (pintype "passive"))
      (node (ref "C10") (pin "1") (pinfunction "1_1") (pintype "passive"))
      (node (ref "C11") (pin "1") (pinfunction "1_1") (pintype "passive"))
      (node (ref "C15") (pin "1") (pinfunction "1_1") (pintype "passive"))
      (node (ref "C16") (pin "1") (pinfunction "1_1") (pintype "passive"))
      (node (ref "C2") (pin "2") (pinfunction "2_2") (pintype "passive"))
      (node (ref "C20") (pin "1") (pinfunction "1_1") (pintype "passive"))
      (node (ref "C21") (pin "1") (pinfunction "1_1") (pintype "passive"))
      (node (ref "C3") (pin "1") (pinfunction "1_1") (pintype "passive"))
      (node (ref "C4") (pin "2") (pinfunction "2_2") (pintype "passive"))
      (node (ref "C5") (pin "1") (pinfunction "1_1") (pintype "passive"))
      (node (ref "C6") (pin "2") (pinfunction "2_2") (pintype "passive"))
      (node (ref "CC1") (pin "2") (pinfunction "GND_2") (pintype "input"))
      (node (ref "CC2") (pin "2") (pinfunction "GND_2") (pintype "input"))
      (node (ref "CC3") (pin "2") (pinfunction "GND_2") (pintype "input"))
      (node (ref "P1") (pin "5") (pinfunction "5_5") (pintype "passive"))
      (node (ref "P1") (pin "6") (pinfunction "6_6") (pintype "passive"))
      (node (ref "P2") (pin "5") (pinfunction "5_5") (pintype "passive"))
      (node (ref "P2") (pin "6") (pinfunction "6_6") (pintype "passive"))
      (node (ref "P3") (pin "5") (pinfunction "5_5") (pintype "passive"))
      (node (ref "P3") (pin "6") (pinfunction "6_6") (pintype "passive"))
      (node (ref "P4") (pin "2") (pinfunction "2_2") (pintype "passive"))
      (node (ref "R11") (pin "1") (pinfunction "1_1") (pintype "passive"))
      (node (ref "R14") (pin "1") (pinfunction "1_1") (pintype "passive"))
      (node (ref "R17") (pin "1") (pinfunction "1_1") (pintype "passive"))
      (node (ref "R3") (pin "1") (pinfunction "1_1") (pintype "passive"))
      (node (ref "R6") (pin "1") (pinfunction "1_1") (pintype "passive"))
      (node (ref "R9") (pin "1") (pinfunction "1_1") (pintype "passive"))
      (node (ref "STM1") (pin "19") (pinfunction "GND_19") (pintype "passive"))
      (node (ref "STM1") (pin "20") (pinfunction "GND_20") (pintype "passive"))
      (node (ref "STM1") (pin "39") (pinfunction "GND_39") (pintype "passive"))
      (node (ref "U1") (pin "2") (pinfunction "GND_2") (pintype "passive"))
      (node (ref "U2") (pin "5") (pinfunction "GND2_5") (pintype "passive"))
      (node (ref "U2") (pin "6") (pinfunction "Out-_6") (pintype "passive"))
      (node (ref "U3") (pin "2") (pinfunction "GND_2") (pintype "passive"))
      (node (ref "U4") (pin "5") (pinfunction "GND2_5") (pintype "passive"))
      (node (ref "U4") (pin "6") (pinfunction "Out-_6") (pintype "passive"))
      (node (ref "U5") (pin "2") (pinfunction "GND_2") (pintype "passive"))
      (node (ref "U6") (pin "5") (pinfunction "GND2_5") (pintype "passive"))
      (node (ref "U6") (pin "6") (pinfunction "Out-_6") (pintype "passive"))
    )
    (net (code "32") (name "Net-(CC1-Vout)") (class "Default")
      (node (ref "CC1") (pin "3") (pinfunction "Vout_3") (pintype "output"))
      (node (ref "R1") (pin "1") (pinfunction "1_1") (pintype "passive"))
    )
    (net (code "33") (name "Net-(CC2-Vout)") (class "Default")
      (node (ref "CC2") (pin "3") (pinfunction "Vout_3") (pintype "output"))
      (node (ref "R4") (pin "1") (pinfunction "1_1") (pintype "passive"))
    )
    (net (code "34") (name "Net-(CC3-Vout)") (class "Default")
      (node (ref "CC3") (pin "3") (pinfunction "Vout_3") (pintype "output"))
      (node (ref "R7") (pin "1") (pinfunction "1_1") (pintype "passive"))
    )
    (net (code "35") (name "Net-(R21-Pad2)") (class "Default")
      (node (ref "R21") (pin "2") (pinfunction "2_2") (pintype "passive"))
      (node (ref "R22") (pin "1") (pinfunction "1_1") (pintype "passive"))
    )
    (net (code "36") (name "Net-(R22-Pad2)") (class "Default")
      (node (ref "R22") (pin "2") (pinfunction "2_2") (pintype "passive"))
      (node (ref "R23") (pin "1") (pinfunction "1_1") (pintype "passive"))
    )
    (net (code "37") (name "Net-(R23-Pad2)") (class "Default")
      (node (ref "R23") (pin "2") (pinfunction "2_2") (pintype "passive"))
      (node (ref "R24") (pin "1") (pinfunction "1_1") (pintype "passive"))
    )
    (net (code "38") (name "Net-(R24-Pad2)") (class "Default")
      (node (ref "R24") (pin "2") (pinfunction "2_2") (pintype "passive"))
      (node (ref "R25") (pin "1") (pinfunction "1_1") (pintype "passive"))
    )
    (net (code "39") (name "Net-(R25-Pad2)") (class "Default")
      (node (ref "R25") (pin "2") (pinfunction "2_2") (pintype "passive"))
      (node (ref "R26") (pin "1") (pinfunction "1_1") (pintype "passive"))
    )
    (net (code "40") (name "Net-(R26-Pad2)") (class "Default")
      (node (ref "R26") (pin "2") (pinfunction "2_2") (pintype "passive"))
      (node (ref "R27") (pin "1") (pinfunction "1_1") (pintype "passive"))
    )
    (net (code "41") (name "Net-(R27-Pad2)") (class "Default")
      (node (ref "R27") (pin "2") (pinfunction "2_2") (pintype "passive"))
      (node (ref "R28") (pin "1") (pinfunction "1_1") (pintype "passive"))
    )
    (net (code "42") (name "Net-(R28-Pad2)") (class "Default")
      (node (ref "R28") (pin "2") (pinfunction "2_2") (pintype "passive"))
      (node (ref "R29") (pin "1") (pinfunction "1_1") (pintype "passive"))
    )
    (net (code "43") (name "Net-(R29-Pad2)") (class "Default")
      (node (ref "R29") (pin "2") (pinfunction "2_2") (pintype "passive"))
      (node (ref "R30") (pin "1") (pinfunction "1_1") (pintype "passive"))
    )
    (net (code "44") (name "Net-(R30-Pad2)") (class "Default")
      (node (ref "R30") (pin "2") (pinfunction "2_2") (pintype "passive"))
      (node (ref "R31") (pin "1") (pinfunction "1_1") (pintype "passive"))
    )
    (net (code "45") (name "Net-(R31-Pad2)") (class "Default")
      (node (ref "R31") (pin "2") (pinfunction "2_2") (pintype "passive"))
      (node (ref "R32") (pin "1") (pinfunction "1_1") (pintype "passive"))
    )
    (net (code "46") (name "Net-(R32-Pad2)") (class "Default")
      (node (ref "R32") (pin "2") (pinfunction "2_2") (pintype "passive"))
      (node (ref "R33") (pin "1") (pinfunction "1_1") (pintype "passive"))
    )
    (net (code "47") (name "Net-(R33-Pad2)") (class "Default")
      (node (ref "R33") (pin "2") (pinfunction "2_2") (pintype "passive"))
      (node (ref "R34") (pin "1") (pinfunction "1_1") (pintype "passive"))
    )
    (net (code "48") (name "Net-(R36-Pad2)") (class "Default")
      (node (ref "R36") (pin "2") (pinfunction "2_2") (pintype "passive"))
      (node (ref "R37") (pin "1") (pinfunction "1_1") (pintype "passive"))
    )
    (net (code "49") (name "Net-(R37-Pad2)") (class "Default")
      (node (ref "R37") (pin "2") (pinfunction "2_2") (pintype "passive"))
      (node (ref "R38") (pin "1") (pinfunction "1_1") (pintype "passive"))
    )
    (net (code "50") (name "Net-(R38-Pad2)") (class "Default")
      (node (ref "R38") (pin "2") (pinfunction "2_2") (pintype "passive"))
      (node (ref "R39") (pin "1") (pinfunction "1_1") (pintype "passive"))
    )
    (net (code "51") (name "Net-(R39-Pad2)") (class "Default")
      (node (ref "R39") (pin "2") (pinfunction "2_2") (pintype "passive"))
      (node (ref "R40") (pin "1") (pinfunction "1_1") (pintype "passive"))
    )
    (net (code "52") (name "Net-(R40-Pad2)") (class "Default")
      (node (ref "R40") (pin "2") (pinfunction "2_2") (pintype "passive"))
      (node (ref "R41") (pin "1") (pinfunction "1_1") (pintype "passive"))
    )
    (net (code "53") (name "Net-(R41-Pad2)") (class "Default")
      (node (ref "R41") (pin "2") (pinfunction "2_2") (pintype "passive"))
      (node (ref "R42") (pin "1") (pinfunction "1_1") (pintype "passive"))
    )
    (net (code "54") (name "Net-(R42-Pad2)") (class "Default")
      (node (ref "R42") (pin "2") (pinfunction "2_2") (pintype "passive"))
      (node (ref "R43") (pin "1") (pinfunction "1_1") (pintype "passive"))
    )
    (net (code "55") (name "Net-(R43-Pad2)") (class "Default")
      (node (ref "R43") (pin "2") (pinfunction "2_2") (pintype "passive"))
      (node (ref "R44") (pin "1") (pinfunction "1_1") (pintype "passive"))
    )
    (net (code "56") (name "Net-(R44-Pad2)") (class "Default")
      (node (ref "R44") (pin "2") (pinfunction "2_2") (pintype "passive"))
      (node (ref "R45") (pin "1") (pinfunction "1_1") (pintype "passive"))
    )
    (net (code "57") (name "Net-(R45-Pad2)") (class "Default")
      (node (ref "R45") (pin "2") (pinfunction "2_2") (pintype "passive"))
      (node (ref "R46") (pin "1") (pinfunction "1_1") (pintype "passive"))
    )
    (net (code "58") (name "Net-(R46-Pad2)") (class "Default")
      (node (ref "R46") (pin "2") (pinfunction "2_2") (pintype "passive"))
      (node (ref "R47") (pin "1") (pinfunction "1_1") (pintype "passive"))
    )
    (net (code "59") (name "Net-(R47-Pad2)") (class "Default")
      (node (ref "R47") (pin "2") (pinfunction "2_2") (pintype "passive"))
      (node (ref "R48") (pin "1") (pinfunction "1_1") (pintype "passive"))
    )
    (net (code "60") (name "Net-(R48-Pad2)") (class "Default")
      (node (ref "R48") (pin "2") (pinfunction "2_2") (pintype "passive"))
      (node (ref "R49") (pin "1") (pinfunction "1_1") (pintype "passive"))
    )
    (net (code "61") (name "Net-(R50-Pad2)") (class "Default")
      (node (ref "R50") (pin "2") (pinfunction "2_2") (pintype "passive"))
      (node (ref "R51") (pin "1") (pinfunction "1_1") (pintype "passive"))
    )
    (net (code "62") (name "Net-(R51-Pad2)") (class "Default")
      (node (ref "R51") (pin "2") (pinfunction "2_2") (pintype "passive"))
      (node (ref "R52") (pin "1") (pinfunction "1_1") (pintype "passive"))
    )
    (net (code "63") (name "Net-(R52-Pad2)") (class "Default")
      (node (ref "R52") (pin "2") (pinfunction "2_2") (pintype "passive"))
      (node (ref "R53") (pin "1") (pinfunction "1_1") (pintype "passive"))
    )
    (net (code "64") (name "Net-(R53-Pad2)") (class "Default")
      (node (ref "R53") (pin "2") (pinfunction "2_2") (pintype "passive"))
      (node (ref "R54") (pin "1") (pinfunction "1_1") (pintype "passive"))
    )
    (net (code "65") (name "Net-(R54-Pad2)") (class "Default")
      (node (ref "R54") (pin "2") (pinfunction "2_2") (pintype "passive"))
      (node (ref "R55") (pin "1") (pinfunction "1_1") (pintype "passive"))
    )
    (net (code "66") (name "Net-(R55-Pad2)") (class "Default")
      (node (ref "R55") (pin "2") (pinfunction "2_2") (pintype "passive"))
      (node (ref "R56") (pin "1") (pinfunction "1_1") (pintype "passive"))
    )
    (net (code "67") (name "Net-(R56-Pad2)") (class "Default")
      (node (ref "R56") (pin "2") (pinfunction "2_2") (pintype "passive"))
      (node (ref "R57") (pin "1") (pinfunction "1_1") (pintype "passive"))
    )
    (net (code "68") (name "Net-(R57-Pad2)") (class "Default")
      (node (ref "R57") (pin "2") (pinfunction "2_2") (pintype "passive"))
      (node (ref "R58") (pin "1") (pinfunction "1_1") (pintype "passive"))
    )
    (net (code "69") (name "Net-(R58-Pad2)") (class "Default")
      (node (ref "R58") (pin "2") (pinfunction "2_2") (pintype "passive"))
      (node (ref "R59") (pin "1") (pinfunction "1_1") (pintype "passive"))
    )
    (net (code "70") (name "Net-(R59-Pad2)") (class "Default")
      (node (ref "R59") (pin "2") (pinfunction "2_2") (pintype "passive"))
      (node (ref "R60") (pin "1") (pinfunction "1_1") (pintype "passive"))
    )
    (net (code "71") (name "Net-(R60-Pad2)") (class "Default")
      (node (ref "R60") (pin "2") (pinfunction "2_2") (pintype "passive"))
      (node (ref "R61") (pin "1") (pinfunction "1_1") (pintype "passive"))
    )
    (net (code "72") (name "Net-(R61-Pad2)") (class "Default")
      (node (ref "R61") (pin "2") (pinfunction "2_2") (pintype "passive"))
      (node (ref "R62") (pin "1") (pinfunction "1_1") (pintype "passive"))
    )
    (net (code "73") (name "Net-(R62-Pad2)") (class "Default")
      (node (ref "R62") (pin "2") (pinfunction "2_2") (pintype "passive"))
      (node (ref "R63") (pin "1") (pinfunction "1_1") (pintype "passive"))
    )
    (net (code "74") (name "Net-(R64-Pad2)") (class "Default")
      (node (ref "R64") (pin "2") (pinfunction "2_2") (pintype "passive"))
      (node (ref "R65") (pin "1") (pinfunction "1_1") (pintype "passive"))
    )
    (net (code "75") (name "Net-(R65-Pad2)") (class "Default")
      (node (ref "R65") (pin "2") (pinfunction "2_2") (pintype "passive"))
      (node (ref "R66") (pin "1") (pinfunction "1_1") (pintype "passive"))
    )
    (net (code "76") (name "Net-(R66-Pad2)") (class "Default")
      (node (ref "R66") (pin "2") (pinfunction "2_2") (pintype "passive"))
      (node (ref "R67") (pin "1") (pinfunction "1_1") (pintype "passive"))
    )
    (net (code "77") (name "Net-(R67-Pad2)") (class "Default")
      (node (ref "R67") (pin "2") (pinfunction "2_2") (pintype "passive"))
      (node (ref "R68") (pin "1") (pinfunction "1_1") (pintype "passive"))
    )
    (net (code "78") (name "Net-(R68-Pad2)") (class "Default")
      (node (ref "R68") (pin "2") (pinfunction "2_2") (pintype "passive"))
      (node (ref "R69") (pin "1") (pinfunction "1_1") (pintype "passive"))
    )
    (net (code "79") (name "Net-(R69-Pad2)") (class "Default")
      (node (ref "R69") (pin "2") (pinfunction "2_2") (pintype "passive"))
      (node (ref "R70") (pin "1") (pinfunction "1_1") (pintype "passive"))
    )
    (net (code "80") (name "Net-(R70-Pad2)") (class "Default")
      (node (ref "R70") (pin "2") (pinfunction "2_2") (pintype "passive"))
      (node (ref "R71") (pin "1") (pinfunction "1_1") (pintype "passive"))
    )
    (net (code "81") (name "Net-(R71-Pad2)") (class "Default")
      (node (ref "R71") (pin "2") (pinfunction "2_2") (pintype "passive"))
      (node (ref "R72") (pin "1") (pinfunction "1_1") (pintype "passive"))
    )
    (net (code "82") (name "Net-(R72-Pad2)") (class "Default")
      (node (ref "R72") (pin "2") (pinfunction "2_2") (pintype "passive"))
      (node (ref "R73") (pin "1") (pinfunction "1_1") (pintype "passive"))
    )
    (net (code "83") (name "Net-(R73-Pad2)") (class "Default")
      (node (ref "R73") (pin "2") (pinfunction "2_2") (pintype "passive"))
      (node (ref "R74") (pin "1") (pinfunction "1_1") (pintype "passive"))
    )
    (net (code "84") (name "Net-(R74-Pad2)") (class "Default")
      (node (ref "R74") (pin "2") (pinfunction "2_2") (pintype "passive"))
      (node (ref "R75") (pin "1") (pinfunction "1_1") (pintype "passive"))
    )
    (net (code "85") (name "Net-(R75-Pad2)") (class "Default")
      (node (ref "R75") (pin "2") (pinfunction "2_2") (pintype "passive"))
      (node (ref "R76") (pin "1") (pinfunction "1_1") (pintype "passive"))
    )
    (net (code "86") (name "Net-(R76-Pad2)") (class "Default")
      (node (ref "R76") (pin "2") (pinfunction "2_2") (pintype "passive"))
      (node (ref "R77") (pin "1") (pinfunction "1_1") (pintype "passive"))
    )
    (net (code "87") (name "Net-(R78-Pad2)") (class "Default")
      (node (ref "R78") (pin "2") (pinfunction "2_2") (pintype "passive"))
      (node (ref "R79") (pin "1") (pinfunction "1_1") (pintype "passive"))
    )
    (net (code "88") (name "Net-(R79-Pad2)") (class "Default")
      (node (ref "R79") (pin "2") (pinfunction "2_2") (pintype "passive"))
      (node (ref "R80") (pin "1") (pinfunction "1_1") (pintype "passive"))
    )
    (net (code "89") (name "Net-(R80-Pad2)") (class "Default")
      (node (ref "R80") (pin "2") (pinfunction "2_2") (pintype "passive"))
      (node (ref "R81") (pin "1") (pinfunction "1_1") (pintype "passive"))
    )
    (net (code "90") (name "Net-(R81-Pad2)") (class "Default")
      (node (ref "R81") (pin "2") (pinfunction "2_2") (pintype "passive"))
      (node (ref "R82") (pin "1") (pinfunction "1_1") (pintype "passive"))
    )
    (net (code "91") (name "Net-(R82-Pad2)") (class "Default")
      (node (ref "R82") (pin "2") (pinfunction "2_2") (pintype "passive"))
      (node (ref "R83") (pin "1") (pinfunction "1_1") (pintype "passive"))
    )
    (net (code "92") (name "Net-(R83-Pad2)") (class "Default")
      (node (ref "R83") (pin "2") (pinfunction "2_2") (pintype "passive"))
      (node (ref "R84") (pin "1") (pinfunction "1_1") (pintype "passive"))
    )
    (net (code "93") (name "Net-(R84-Pad2)") (class "Default")
      (node (ref "R84") (pin "2") (pinfunction "2_2") (pintype "passive"))
      (node (ref "R85") (pin "1") (pinfunction "1_1") (pintype "passive"))
    )
    (net (code "94") (name "Net-(R85-Pad2)") (class "Default")
      (node (ref "R85") (pin "2") (pinfunction "2_2") (pintype "passive"))
      (node (ref "R86") (pin "1") (pinfunction "1_1") (pintype "passive"))
    )
    (net (code "95") (name "Net-(R86-Pad2)") (class "Default")
      (node (ref "R86") (pin "2") (pinfunction "2_2") (pintype "passive"))
      (node (ref "R87") (pin "1") (pinfunction "1_1") (pintype "passive"))
    )
    (net (code "96") (name "Net-(R87-Pad2)") (class "Default")
      (node (ref "R87") (pin "2") (pinfunction "2_2") (pintype "passive"))
      (node (ref "R88") (pin "1") (pinfunction "1_1") (pintype "passive"))
    )
    (net (code "97") (name "Net-(R88-Pad2)") (class "Default")
      (node (ref "R88") (pin "2") (pinfunction "2_2") (pintype "passive"))
      (node (ref "R89") (pin "1") (pinfunction "1_1") (pintype "passive"))
    )
    (net (code "98") (name "Net-(R89-Pad2)") (class "Default")
      (node (ref "R89") (pin "2") (pinfunction "2_2") (pintype "passive"))
      (node (ref "R90") (pin "1") (pinfunction "1_1") (pintype "passive"))
    )
    (net (code "99") (name "Net-(R90-Pad2)") (class "Default")
      (node (ref "R90") (pin "2") (pinfunction "2_2") (pintype "passive"))
      (node (ref "R91") (pin "1") (pinfunction "1_1") (pintype "passive"))
    )
    (net (code "100") (name "Net-(R92-Pad2)") (class "Default")
      (node (ref "R92") (pin "2") (pinfunction "2_2") (pintype "passive"))
      (node (ref "R93") (pin "1") (pinfunction "1_1") (pintype "passive"))
    )
    (net (code "101") (name "Net-(R93-Pad2)") (class "Default")
      (node (ref "R93") (pin "2") (pinfunction "2_2") (pintype "passive"))
      (node (ref "R94") (pin "1") (pinfunction "1_1") (pintype "passive"))
    )
    (net (code "102") (name "Net-(R94-Pad2)") (class "Default")
      (node (ref "R94") (pin "2") (pinfunction "2_2") (pintype "passive"))
      (node (ref "R95") (pin "1") (pinfunction "1_1") (pintype "passive"))
    )
    (net (code "103") (name "Net-(R95-Pad2)") (class "Default")
      (node (ref "R95") (pin "2") (pinfunction "2_2") (pintype "passive"))
      (node (ref "R96") (pin "1") (pinfunction "1_1") (pintype "passive"))
    )
    (net (code "104") (name "Net-(R96-Pad2)") (class "Default")
      (node (ref "R96") (pin "2") (pinfunction "2_2") (pintype "passive"))
      (node (ref "R97") (pin "1") (pinfunction "1_1") (pintype "passive"))
    )
    (net (code "105") (name "Net-(R97-Pad2)") (class "Default")
      (node (ref "R97") (pin "2") (pinfunction "2_2") (pintype "passive"))
      (node (ref "R98") (pin "1") (pinfunction "1_1") (pintype "passive"))
    )
    (net (code "106") (name "Net-(R98-Pad2)") (class "Default")
      (node (ref "R98") (pin "2") (pinfunction "2_2") (pintype "passive"))
      (node (ref "R99") (pin "1") (pinfunction "1_1") (pintype "passive"))
    )
    (net (code "107") (name "Net-(R100-Pad1)") (class "Default")
      (node (ref "R100") (pin "1") (pinfunction "1_1") (pintype "passive"))
      (node (ref "R99") (pin "2") (pinfunction "2_2") (pintype "passive"))
    )
    (net (code "108") (name "Net-(R100-Pad2)") (class "Default")
      (node (ref "R100") (pin "2") (pinfunction "2_2") (pintype "passive"))
      (node (ref "R101") (pin "1") (pinfunction "1_1") (pintype "passive"))
    )
    (net (code "109") (name "Net-(R101-Pad2)") (class "Default")
      (node (ref "R101") (pin "2") (pinfunction "2_2") (pintype "passive"))
      (node (ref "R102") (pin "1") (pinfunction "1_1") (pintype "passive"))
    )
    (net (code "110") (name "Net-(R102-Pad2)") (class "Default")
      (node (ref "R102") (pin "2") (pinfunction "2_2") (pintype "passive"))
      (node (ref "R103") (pin "1") (pinfunction "1_1") (pintype "passive"))
    )
    (net (code "111") (name "Net-(R103-Pad2)") (class "Default")
      (node (ref "R103") (pin "2") (pinfunction "2_2") (pintype "passive"))
      (node (ref "R104") (pin "1") (pinfunction "1_1") (pintype "passive"))
    )
    (net (code "112") (name "Net-(R104-Pad2)") (class "Default")
      (node (ref "R104") (pin "2") (pinfunction "2_2") (pintype "passive"))
      (node (ref "R105") (pin "1") (pinfunction "1_1") (pintype "passive"))
    )
    (net (code "113") (name "Net-(U2-Out+)") (class "Default")
      (node (ref "R13") (pin "1") (pinfunction "1_1") (pintype "passive"))
      (node (ref "U2") (pin "7") (pinfunction "Out+_7") (pintype "passive"))
    )
    (net (code "114") (name "Net-(U4-Out+)") (class "Default")
      (node (ref "R18") (pin "1") (pinfunction "1_1") (pintype "passive"))
      (node (ref "U4") (pin "7") (pinfunction "Out+_7") (pintype "passive"))
    )
    (net (code "115") (name "Net-(U6-Out+)") (class "Default")
      (node (ref "R20") (pin "1") (pinfunction "1_1") (pintype "passive"))
      (node (ref "U6") (pin "7") (pinfunction "Out+_7") (pintype "passive"))
    )
    (net (code "116") (name "VCC") (class "Default")
      (node (ref "C1") (pin "2") (pinfunction "2_2") (pintype "passive"))
      (node (ref "C11") (pin "2") (pinfunction "2_2") (pintype "passive"))
      (node (ref "C16") (pin "2") (pinfunction "2_2") (pintype "passive"))
      (node (ref "C21") (pin "2") (pinfunction "2_2") (pintype "passive"))
      (node (ref "C3") (pin "2") (pinfunction "2_2") (pintype "passive"))
      (node (ref "C5") (pin "2") (pinfunction "2_2") (pintype "passive"))
      (node (ref "CC1") (pin "1") (pinfunction "VCC_1") (pintype "input"))
      (node (ref "CC2") (pin "1") (pinfunction "VCC_1") (pintype "input"))
      (node (ref "CC3") (pin "1") (pinfunction "VCC_1") (pintype "input"))
      (node (ref "P1") (pin "1") (pinfunction "1_1") (pintype "passive"))
      (node (ref "P1") (pin "2") (pinfunction "2_2") (pintype "passive"))
      (node (ref "P2") (pin "1") (pinfunction "1_1") (pintype "passive"))
      (node (ref "P2") (pin "2") (pinfunction "2_2") (pintype "passive"))
      (node (ref "P3") (pin "1") (pinfunction "1_1") (pintype "passive"))
      (node (ref "P3") (pin "2") (pinfunction "2_2") (pintype "passive"))
      (node (ref "P4") (pin "1") (pinfunction "1_1") (pintype "passive"))
      (node (ref "STM1") (pin "38") (pinfunction "5V_38") (pintype "passive"))
      (node (ref "U1") (pin "1") (pinfunction "Vin_1") (pintype "passive"))
      (node (ref "U2") (pin "8") (pinfunction "VDD2_8") (pintype "passive"))
      (node (ref "U3") (pin "1") (pinfunction "Vin_1") (pintype "passive"))
      (node (ref "U4") (pin "8") (pinfunction "VDD2_8") (pintype "passive"))
      (node (ref "U5") (pin "1") (pinfunction "Vin_1") (pintype "passive"))
      (node (ref "U6") (pin "8") (pinfunction "VDD2_8") (pintype "passive"))
    )
    (net (code "117") (name "unconnected-(STM1-3V3-Pad18)") (class "Default")
      (node (ref "STM1") (pin "18") (pinfunction "3V3_18") (pintype "passive"))
    )
    (net (code "118") (name "unconnected-(STM1-3V3-Pad40)") (class "Default")
      (node (ref "STM1") (pin "40") (pinfunction "3V3_40") (pintype "passive"))
    )
    (net (code "119") (name "unconnected-(STM1-PA_6-Pad11)") (class "Default")
      (node (ref "STM1") (pin "11") (pinfunction "PA_6_11") (pintype "passive"))
    )
    (net (code "120") (name "unconnected-(STM1-PA_7-Pad12)") (class "Default")
      (node (ref "STM1") (pin "12") (pinfunction "PA_7_12") (pintype "passive"))
    )
    (net (code "121") (name "unconnected-(STM1-PA_8-Pad25)") (class "Default")
      (node (ref "STM1") (pin "25") (pinfunction "PA_8_25") (pintype "passive"))
    )
    (net (code "122") (name "unconnected-(STM1-PA_9-Pad26)") (class "Default")
      (node (ref "STM1") (pin "26") (pinfunction "PA_9_26") (pintype "passive"))
    )
    (net (code "123") (name "unconnected-(STM1-PA_10-Pad27)") (class "Default")
      (node (ref "STM1") (pin "27") (pinfunction "PA_10_27") (pintype "passive"))
    )
    (net (code "124") (name "unconnected-(STM1-PA_11-Pad28)") (class "Default")
      (node (ref "STM1") (pin "28") (pinfunction "PA_11_28") (pintype "passive"))
    )
    (net (code "125") (name "unconnected-(STM1-PA_12-Pad29)") (class "Default")
      (node (ref "STM1") (pin "29") (pinfunction "PA_12_29") (pintype "passive"))
    )
    (net (code "126") (name "unconnected-(STM1-PA_15-Pad30)") (class "Default")
      (node (ref "STM1") (pin "30") (pinfunction "PA_15_30") (pintype "passive"))
    )
    (net (code "127") (name "unconnected-(STM1-PB_0-Pad13)") (class "Default")
      (node (ref "STM1") (pin "13") (pinfunction "PB_0_13") (pintype "passive"))
    )
    (net (code "128") (name "unconnected-(STM1-PB_1-Pad14)") (class "Default")
      (node (ref "STM1") (pin "14") (pinfunction "PB_1_14") (pintype "passive"))
    )
    (net (code "129") (name "unconnected-(STM1-PB_3-Pad31)") (class "Default")
      (node (ref "STM1") (pin "31") (pinfunction "PB_3_31") (pintype "passive"))
    )
    (net (code "130") (name "unconnected-(STM1-PB_4-Pad32)") (class "Default")
      (node (ref "STM1") (pin "32") (pinfunction "PB_4_32") (pintype "passive"))
    )
    (net (code "131") (name "unconnected-(STM1-PB_5-Pad33)") (class "Default")
      (node (ref "STM1") (pin "33") (pinfunction "PB_5_33") (pintype "passive"))
    )
    (net (code "132") (name "unconnected-(STM1-PB_6-Pad34)") (class "Default")
      (node (ref "STM1") (pin "34") (pinfunction "PB_6_34") (pintype "passive"))
    )
    (net (code "133") (name "unconnected-(STM1-PB_7-Pad35)") (class "Default")
      (node (ref "STM1") (pin "35") (pinfunction "PB_7_35") (pintype "passive"))
    )
    (net (code "134") (name "unconnected-(STM1-PB_8-Pad36)") (class "Default")
      (node (ref "STM1") (pin "36") (pinfunction "PB_8_36") (pintype "passive"))
    )
    (net (code "135") (name "unconnected-(STM1-PB_9-Pad37)") (class "Default")
      (node (ref "STM1") (pin "37") (pinfunction "PB_9_37") (pintype "passive"))
    )
    (net (code "136") (name "unconnected-(STM1-PB_10-Pad15)") (class "Default")
      (node (ref "STM1") (pin "15") (pinfunction "PB_10_15") (pintype "passive"))
    )
    (net (code "137") (name "unconnected-(STM1-PB_11-Pad16)") (class "Default")
      (node (ref "STM1") (pin "16") (pinfunction "PB_11_16") (pintype "passive"))
    )
    (net (code "138") (name "unconnected-(STM1-PB_12-Pad21)") (class "Default")
      (node (ref "STM1") (pin "21") (pinfunction "PB_12_21") (pintype "passive"))
    )
    (net (code "139") (name "unconnected-(STM1-PB_13-Pad22)") (class "Default")
      (node (ref "STM1") (pin "22") (pinfunction "PB_13_22") (pintype "passive"))
    )
    (net (code "140") (name "unconnected-(STM1-PB_14-Pad23)") (class "Default")
      (node (ref "STM1") (pin "23") (pinfunction "PB_14_23") (pintype "passive"))
    )
    (net (code "141") (name "unconnected-(STM1-PB_15-Pad24)") (class "Default")
      (node (ref "STM1") (pin "24") (pinfunction "PB_15_24") (pintype "passive"))
    )
    (net (code "142") (name "unconnected-(STM1-PC_13-Pad2)") (class "Default")
      (node (ref "STM1") (pin "2") (pinfunction "PC_13_2") (pintype "passive"))
    )
    (net (code "143") (name "unconnected-(STM1-PC_14-Pad3)") (class "Default")
      (node (ref "STM1") (pin "3") (pinfunction "PC_14_3") (pintype "passive"))
    )
    (net (code "144") (name "unconnected-(STM1-PC_15-Pad4)") (class "Default")
      (node (ref "STM1") (pin "4") (pinfunction "PC_15_4") (pintype "passive"))
    )
    (net (code "145") (name "unconnected-(STM1-RESET-Pad17)") (class "Default")
      (node (ref "STM1") (pin "17") (pinfunction "RESET_17") (pintype "passive"))
    )
    (net (code "146") (name "unconnected-(STM1-Vbat-Pad1)") (class "Default")
      (node (ref "STM1") (pin "1") (pinfunction "Vbat_1") (pintype "passive"))
    )
  )
)
